# schSensorChassiNano.net
KiCad netlist of a schematic drawn in Altium Designer
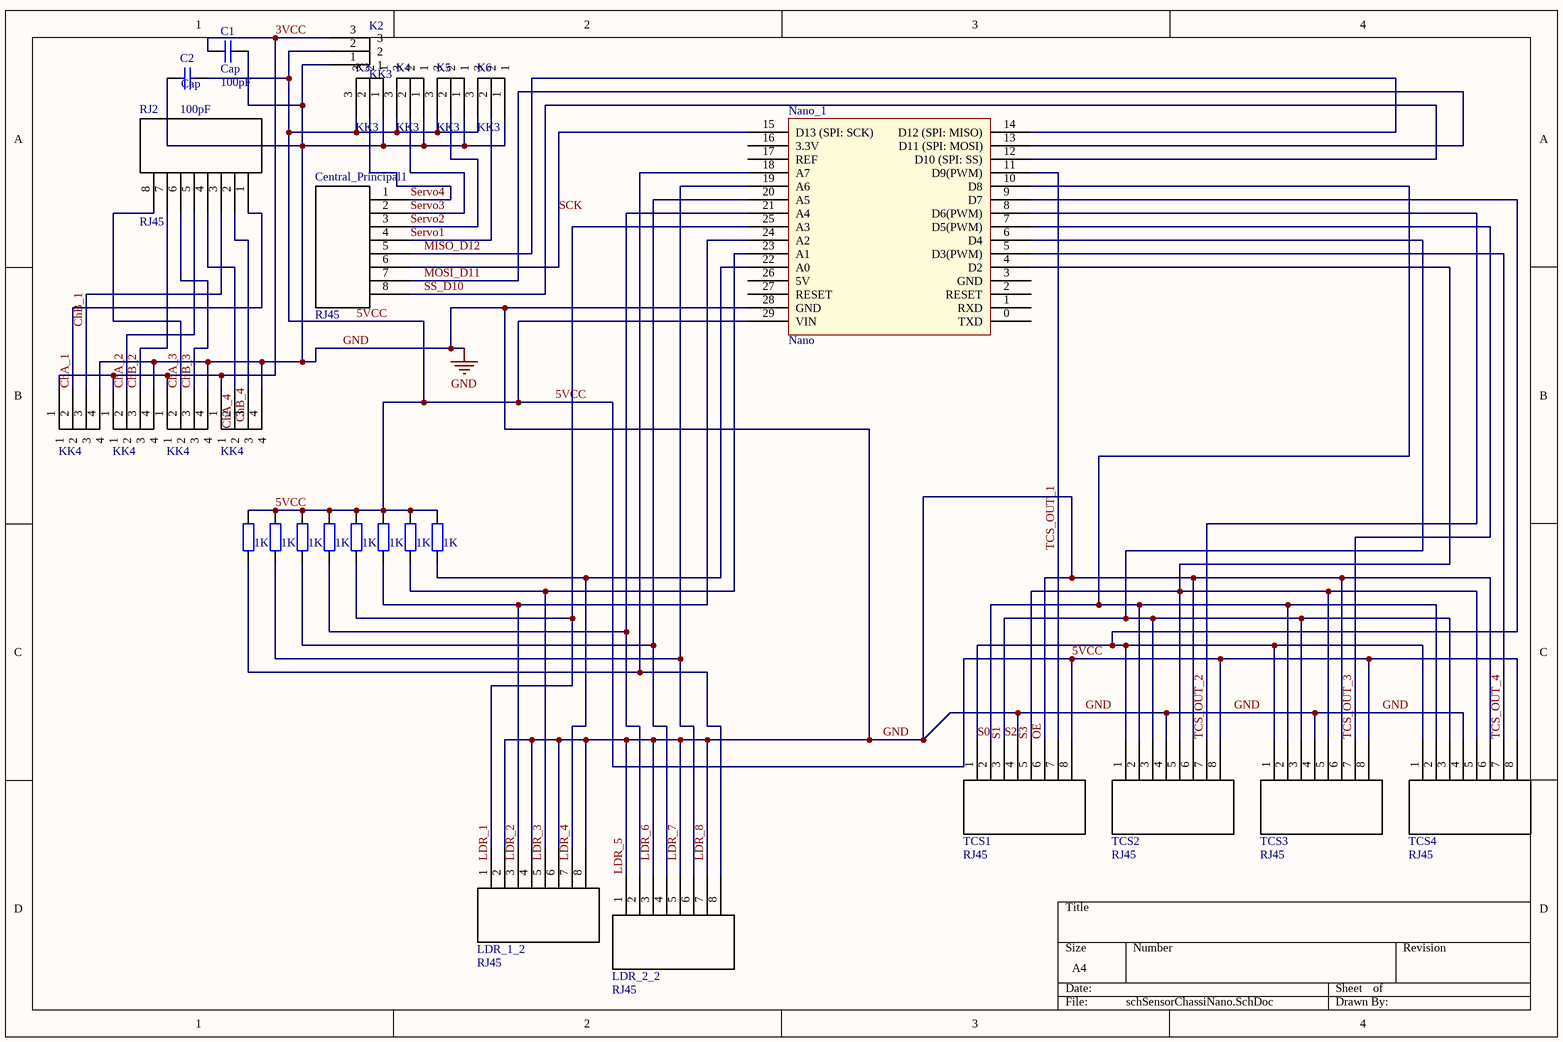
[diagram p0: schSensorChassiNano.SchDoc]

(export (version "E")
  (design (tool "Eeschema 10.0.6"))
  (components
    (comp (ref "C1")
      (value "Cap")
      (footprint "RAD-0.3")
      (description "Capacitor")
      (fields (field (name "ALTIUM_VALUE") "100pF") (field (name "PUBLISHER") "Altium Limited"))
      (libsource (lib "Miscellaneous Devices") (part "Cap"))
    )
    (comp (ref "C2")
      (value "Cap")
      (footprint "RAD-0.3")
      (description "Capacitor")
      (fields (field (name "ALTIUM_VALUE") "100pF") (field (name "PUBLISHER") "Altium Limited"))
      (libsource (lib "Miscellaneous Devices") (part "Cap"))
    )
    (comp (ref "Central_Principal1")
      (value "RJ45")
      (footprint "RJ45_Simples")
      (libsource (lib "Componentes_Open") (part "RJ45"))
    )
    (comp (ref "Encoder_4")
      (value "KK4")
      (footprint "4-vias")
      (libsource (lib "Componentes_Open") (part "KK4Vias"))
    )
    (comp (ref "Encoder_5")
      (value "KK4")
      (footprint "4-vias")
      (libsource (lib "Componentes_Open") (part "KK4Vias"))
    )
    (comp (ref "Encoder_6")
      (value "KK4")
      (footprint "4-vias")
      (libsource (lib "Componentes_Open") (part "KK4Vias"))
    )
    (comp (ref "K1") (value "KK4") (footprint "4-vias") (libsource (lib "Componentes_Open") (part "KK4Vias")))
    (comp (ref "K2") (value "KK3") (footprint "3-vias") (libsource (lib "Componentes_Open") (part "KK3Vias")))
    (comp (ref "K3") (value "KK3") (footprint "3-vias") (libsource (lib "Componentes_Open") (part "KK3Vias")))
    (comp (ref "K4") (value "KK3") (footprint "3-vias") (libsource (lib "Componentes_Open") (part "KK3Vias")))
    (comp (ref "K5") (value "KK3") (footprint "3-vias") (libsource (lib "Componentes_Open") (part "KK3Vias")))
    (comp (ref "K6") (value "KK3") (footprint "3-vias") (libsource (lib "Componentes_Open") (part "KK3Vias")))
    (comp (ref "LDR_1_2")
      (value "RJ45")
      (footprint "RJ45_Simples")
      (libsource (lib "Componentes_Open") (part "RJ45"))
    )
    (comp (ref "LDR_2_2")
      (value "RJ45")
      (footprint "RJ45_Simples")
      (libsource (lib "Componentes_Open") (part "RJ45"))
    )
    (comp (ref "Nano_1")
      (value "Nano")
      (footprint "Arduino_Nano")
      (libsource (lib "Componentes_Open") (part "Arduino_Nano"))
    )
    (comp (ref "R17")
      (value "1K")
      (footprint "AXIAL-0.4")
      (description "Resistor")
      (fields (field (name "Comment") "Res2") (field (name "PUBLISHER") "Altium Limited"))
      (libsource (lib "Miscellaneous Devices") (part "Res2"))
    )
    (comp (ref "R18")
      (value "1K")
      (footprint "AXIAL-0.4")
      (description "Resistor")
      (fields (field (name "Comment") "Res2") (field (name "PUBLISHER") "Altium Limited"))
      (libsource (lib "Miscellaneous Devices") (part "Res2"))
    )
    (comp (ref "R19")
      (value "1K")
      (footprint "AXIAL-0.4")
      (description "Resistor")
      (fields (field (name "Comment") "Res2") (field (name "PUBLISHER") "Altium Limited"))
      (libsource (lib "Miscellaneous Devices") (part "Res2"))
    )
    (comp (ref "R20")
      (value "1K")
      (footprint "AXIAL-0.4")
      (description "Resistor")
      (fields (field (name "Comment") "Res2") (field (name "PUBLISHER") "Altium Limited"))
      (libsource (lib "Miscellaneous Devices") (part "Res2"))
    )
    (comp (ref "R21")
      (value "1K")
      (footprint "AXIAL-0.4")
      (description "Resistor")
      (fields (field (name "Comment") "Res2") (field (name "PUBLISHER") "Altium Limited"))
      (libsource (lib "Miscellaneous Devices") (part "Res2"))
    )
    (comp (ref "R22")
      (value "1K")
      (footprint "AXIAL-0.4")
      (description "Resistor")
      (fields (field (name "Comment") "Res2") (field (name "PUBLISHER") "Altium Limited"))
      (libsource (lib "Miscellaneous Devices") (part "Res2"))
    )
    (comp (ref "R23")
      (value "1K")
      (footprint "AXIAL-0.4")
      (description "Resistor")
      (fields (field (name "Comment") "Res2") (field (name "PUBLISHER") "Altium Limited"))
      (libsource (lib "Miscellaneous Devices") (part "Res2"))
    )
    (comp (ref "R24")
      (value "1K")
      (footprint "AXIAL-0.4")
      (description "Resistor")
      (fields (field (name "Comment") "Res2") (field (name "PUBLISHER") "Altium Limited"))
      (libsource (lib "Miscellaneous Devices") (part "Res2"))
    )
    (comp (ref "RJ2")
      (value "RJ45")
      (footprint "RJ45_Simples")
      (libsource (lib "Componentes_Open") (part "RJ45"))
    )
    (comp (ref "TCS1")
      (value "RJ45")
      (footprint "RJ45_Simples")
      (libsource (lib "Componentes_Open") (part "RJ45"))
    )
    (comp (ref "TCS2")
      (value "RJ45")
      (footprint "RJ45_Simples")
      (libsource (lib "Componentes_Open") (part "RJ45"))
    )
    (comp (ref "TCS3")
      (value "RJ45")
      (footprint "RJ45_Simples")
      (libsource (lib "Componentes_Open") (part "RJ45"))
    )
    (comp (ref "TCS4")
      (value "RJ45")
      (footprint "RJ45_Simples")
      (libsource (lib "Componentes_Open") (part "RJ45"))
    )
  )
  (nets
    (net (code "1") (name "/3VCC") (class "Default")
      (node (ref "C1") (pin "1") (pinfunction "1_1") (pintype "passive"))
      (node (ref "Encoder_4") (pin "1") (pinfunction "1_1") (pintype "passive"))
      (node (ref "Encoder_5") (pin "1") (pinfunction "1_1") (pintype "passive"))
      (node (ref "Encoder_6") (pin "1") (pinfunction "1_1") (pintype "passive"))
      (node (ref "K1") (pin "1") (pinfunction "1_1") (pintype "passive"))
      (node (ref "K2") (pin "3") (pinfunction "3_3") (pintype "passive"))
    )
    (net (code "2") (name "/5VCC") (class "Default")
      (node (ref "C2") (pin "2") (pinfunction "2_2") (pintype "passive"))
      (node (ref "K2") (pin "2") (pinfunction "2_2") (pintype "passive"))
      (node (ref "K3") (pin "3") (pinfunction "3_3") (pintype "passive"))
      (node (ref "K4") (pin "3") (pinfunction "3_3") (pintype "passive"))
      (node (ref "K5") (pin "3") (pinfunction "3_3") (pintype "passive"))
      (node (ref "K6") (pin "3") (pinfunction "3_3") (pintype "passive"))
      (node (ref "Nano_1") (pin "29") (pinfunction "VIN_29") (pintype "passive"))
      (node (ref "R17") (pin "2") (pinfunction "2_2") (pintype "passive"))
      (node (ref "R18") (pin "2") (pinfunction "2_2") (pintype "passive"))
      (node (ref "R19") (pin "2") (pinfunction "2_2") (pintype "passive"))
      (node (ref "R20") (pin "2") (pinfunction "2_2") (pintype "passive"))
      (node (ref "R21") (pin "2") (pinfunction "2_2") (pintype "passive"))
      (node (ref "R22") (pin "2") (pinfunction "2_2") (pintype "passive"))
      (node (ref "R23") (pin "2") (pinfunction "2_2") (pintype "passive"))
      (node (ref "R24") (pin "2") (pinfunction "2_2") (pintype "passive"))
      (node (ref "TCS1") (pin "8") (pinfunction "8_8") (pintype "passive"))
      (node (ref "TCS2") (pin "8") (pinfunction "8_8") (pintype "passive"))
      (node (ref "TCS3") (pin "8") (pinfunction "8_8") (pintype "passive"))
      (node (ref "TCS4") (pin "8") (pinfunction "8_8") (pintype "passive"))
    )
    (net (code "3") (name "/ChA_1") (class "Default")
      (node (ref "K1") (pin "2") (pinfunction "2_2") (pintype "passive"))
      (node (ref "RJ2") (pin "1") (pinfunction "9_1") (pintype "passive"))
    )
    (net (code "4") (name "/ChA_2") (class "Default")
      (node (ref "Encoder_4") (pin "2") (pinfunction "2_2") (pintype "passive"))
      (node (ref "RJ2") (pin "5") (pinfunction "5_5") (pintype "passive"))
    )
    (net (code "5") (name "/ChA_3") (class "Default")
      (node (ref "Encoder_5") (pin "2") (pinfunction "2_2") (pintype "passive"))
      (node (ref "RJ2") (pin "8") (pinfunction "8_8") (pintype "passive"))
    )
    (net (code "7") (name "/ChB_1") (class "Default")
      (node (ref "K1") (pin "3") (pinfunction "3_3") (pintype "passive"))
      (node (ref "RJ2") (pin "3") (pinfunction "3_3") (pintype "passive"))
    )
    (net (code "8") (name "/ChB_2") (class "Default")
      (node (ref "Encoder_4") (pin "3") (pinfunction "3_3") (pintype "passive"))
      (node (ref "RJ2") (pin "7") (pinfunction "7_7") (pintype "passive"))
    )
    (net (code "9") (name "/ChB_3") (class "Default")
      (node (ref "Encoder_5") (pin "3") (pinfunction "3_3") (pintype "passive"))
      (node (ref "RJ2") (pin "6") (pinfunction "6_6") (pintype "passive"))
    )
    (net (code "15") (name "/MISO_D12") (class "Default")
      (node (ref "Central_Principal1") (pin "5") (pinfunction "5_5") (pintype "passive"))
      (node (ref "Nano_1") (pin "14") (pinfunction "D12_(SPI:_MISO)_14") (pintype "passive"))
    )
    (net (code "16") (name "/MOSI_D11") (class "Default")
      (node (ref "Central_Principal1") (pin "7") (pinfunction "7_7") (pintype "passive"))
      (node (ref "Nano_1") (pin "13") (pinfunction "D11_(SPI:_MOSI)_13") (pintype "passive"))
    )
    (net (code "17") (name "/S0") (class "Default")
      (node (ref "Nano_1") (pin "9") (pinfunction "D7_9") (pintype "passive"))
      (node (ref "TCS1") (pin "1") (pinfunction "9_1") (pintype "passive"))
      (node (ref "TCS2") (pin "1") (pinfunction "9_1") (pintype "passive"))
      (node (ref "TCS3") (pin "1") (pinfunction "9_1") (pintype "passive"))
      (node (ref "TCS4") (pin "1") (pinfunction "9_1") (pintype "passive"))
    )
    (net (code "18") (name "/S1") (class "Default")
      (node (ref "Nano_1") (pin "6") (pinfunction "D4_6") (pintype "passive"))
      (node (ref "TCS1") (pin "3") (pinfunction "3_3") (pintype "passive"))
      (node (ref "TCS2") (pin "3") (pinfunction "3_3") (pintype "passive"))
      (node (ref "TCS3") (pin "3") (pinfunction "3_3") (pintype "passive"))
      (node (ref "TCS4") (pin "3") (pinfunction "3_3") (pintype "passive"))
    )
    (net (code "19") (name "/S3") (class "Default")
      (node (ref "Nano_1") (pin "4") (pinfunction "D2_4") (pintype "passive"))
      (node (ref "TCS1") (pin "5") (pinfunction "5_5") (pintype "passive"))
      (node (ref "TCS2") (pin "5") (pinfunction "5_5") (pintype "passive"))
      (node (ref "TCS3") (pin "5") (pinfunction "5_5") (pintype "passive"))
      (node (ref "TCS4") (pin "5") (pinfunction "5_5") (pintype "passive"))
    )
    (net (code "20") (name "/SCK") (class "Default")
      (node (ref "Central_Principal1") (pin "6") (pinfunction "6_6") (pintype "passive"))
      (node (ref "Nano_1") (pin "15") (pinfunction "D13_(SPI:_SCK)_15") (pintype "passive"))
    )
    (net (code "21") (name "/SS_D10") (class "Default")
      (node (ref "Central_Principal1") (pin "8") (pinfunction "8_8") (pintype "passive"))
      (node (ref "Nano_1") (pin "12") (pinfunction "D10_(SPI:_SS)_12") (pintype "passive"))
    )
    (net (code "22") (name "/Servo1") (class "Default")
      (node (ref "Central_Principal1") (pin "4") (pinfunction "4_4") (pintype "passive"))
      (node (ref "K6") (pin "2") (pinfunction "2_2") (pintype "passive"))
    )
    (net (code "23") (name "/Servo2") (class "Default")
      (node (ref "Central_Principal1") (pin "3") (pinfunction "3_3") (pintype "passive"))
      (node (ref "K5") (pin "2") (pinfunction "2_2") (pintype "passive"))
    )
    (net (code "24") (name "/Servo3") (class "Default")
      (node (ref "Central_Principal1") (pin "2") (pinfunction "2_2") (pintype "passive"))
      (node (ref "K4") (pin "2") (pinfunction "2_2") (pintype "passive"))
    )
    (net (code "25") (name "/Servo4") (class "Default")
      (node (ref "Central_Principal1") (pin "1") (pinfunction "9_1") (pintype "passive"))
      (node (ref "K3") (pin "2") (pinfunction "2_2") (pintype "passive"))
    )
    (net (code "26") (name "/TCS_OUT_1") (class "Default")
      (node (ref "Nano_1") (pin "11") (pinfunction "D9(PWM)_11") (pintype "passive"))
      (node (ref "TCS1") (pin "7") (pinfunction "7_7") (pintype "passive"))
    )
    (net (code "27") (name "/TCS_OUT_2") (class "Default")
      (node (ref "Nano_1") (pin "8") (pinfunction "D6(PWM)_8") (pintype "passive"))
      (node (ref "TCS2") (pin "7") (pinfunction "7_7") (pintype "passive"))
    )
    (net (code "28") (name "/TCS_OUT_3") (class "Default")
      (node (ref "Nano_1") (pin "7") (pinfunction "D5(PWM)_7") (pintype "passive"))
      (node (ref "TCS3") (pin "7") (pinfunction "7_7") (pintype "passive"))
    )
    (net (code "29") (name "/TCS_OUT_4") (class "Default")
      (node (ref "Nano_1") (pin "5") (pinfunction "D3(PWM)_5") (pintype "passive"))
      (node (ref "TCS4") (pin "7") (pinfunction "7_7") (pintype "passive"))
    )
    (net (code "30") (name "GND") (class "Default")
      (node (ref "C1") (pin "2") (pinfunction "2_2") (pintype "passive"))
      (node (ref "C2") (pin "1") (pinfunction "1_1") (pintype "passive"))
      (node (ref "Encoder_4") (pin "4") (pinfunction "4_4") (pintype "passive"))
      (node (ref "Encoder_5") (pin "4") (pinfunction "4_4") (pintype "passive"))
      (node (ref "Encoder_6") (pin "4") (pinfunction "4_4") (pintype "passive"))
      (node (ref "K1") (pin "4") (pinfunction "4_4") (pintype "passive"))
      (node (ref "K2") (pin "1") (pinfunction "1_1") (pintype "passive"))
      (node (ref "K3") (pin "1") (pinfunction "1_1") (pintype "passive"))
      (node (ref "K4") (pin "1") (pinfunction "1_1") (pintype "passive"))
      (node (ref "K5") (pin "1") (pinfunction "1_1") (pintype "passive"))
      (node (ref "K6") (pin "1") (pinfunction "1_1") (pintype "passive"))
      (node (ref "LDR_1_2") (pin "2") (pinfunction "2_2") (pintype "passive"))
      (node (ref "LDR_1_2") (pin "4") (pinfunction "4_4") (pintype "passive"))
      (node (ref "LDR_1_2") (pin "6") (pinfunction "6_6") (pintype "passive"))
      (node (ref "LDR_1_2") (pin "8") (pinfunction "8_8") (pintype "passive"))
      (node (ref "LDR_2_2") (pin "1") (pinfunction "9_1") (pintype "passive"))
      (node (ref "LDR_2_2") (pin "3") (pinfunction "3_3") (pintype "passive"))
      (node (ref "LDR_2_2") (pin "5") (pinfunction "5_5") (pintype "passive"))
      (node (ref "LDR_2_2") (pin "7") (pinfunction "7_7") (pintype "passive"))
      (node (ref "Nano_1") (pin "28") (pinfunction "GND_28") (pintype "passive"))
      (node (ref "TCS1") (pin "4") (pinfunction "4_4") (pintype "passive"))
      (node (ref "TCS1") (pin "6") (pinfunction "6_6") (pintype "passive"))
      (node (ref "TCS2") (pin "4") (pinfunction "4_4") (pintype "passive"))
      (node (ref "TCS2") (pin "6") (pinfunction "6_6") (pintype "passive"))
      (node (ref "TCS3") (pin "4") (pinfunction "4_4") (pintype "passive"))
      (node (ref "TCS3") (pin "6") (pinfunction "6_6") (pintype "passive"))
      (node (ref "TCS4") (pin "4") (pinfunction "4_4") (pintype "passive"))
      (node (ref "TCS4") (pin "6") (pinfunction "6_6") (pintype "passive"))
    )
    (net (code "31") (name "Net-(Encoder_6-Pad2)") (class "Default")
      (node (ref "Encoder_6") (pin "2") (pinfunction "2_2") (pintype "passive"))
      (node (ref "RJ2") (pin "4") (pinfunction "4_4") (pintype "passive"))
    )
    (net (code "32") (name "Net-(Encoder_6-Pad3)") (class "Default")
      (node (ref "Encoder_6") (pin "3") (pinfunction "3_3") (pintype "passive"))
      (node (ref "RJ2") (pin "2") (pinfunction "2_2") (pintype "passive"))
    )
    (net (code "33") (name "Net-(LDR_1_2-9)") (class "Default")
      (node (ref "LDR_1_2") (pin "1") (pinfunction "9_1") (pintype "passive"))
      (node (ref "Nano_1") (pin "25") (pinfunction "A3_25") (pintype "passive"))
      (node (ref "R21") (pin "1") (pinfunction "1_1") (pintype "passive"))
    )
    (net (code "34") (name "Net-(Nano_1-A0)") (class "Default")
      (node (ref "LDR_1_2") (pin "7") (pinfunction "7_7") (pintype "passive"))
      (node (ref "Nano_1") (pin "22") (pinfunction "A0_22") (pintype "passive"))
      (node (ref "R24") (pin "1") (pinfunction "1_1") (pintype "passive"))
    )
    (net (code "35") (name "Net-(Nano_1-A1)") (class "Default")
      (node (ref "LDR_1_2") (pin "5") (pinfunction "5_5") (pintype "passive"))
      (node (ref "Nano_1") (pin "23") (pinfunction "A1_23") (pintype "passive"))
      (node (ref "R23") (pin "1") (pinfunction "1_1") (pintype "passive"))
    )
    (net (code "36") (name "Net-(Nano_1-A2)") (class "Default")
      (node (ref "LDR_1_2") (pin "3") (pinfunction "3_3") (pintype "passive"))
      (node (ref "Nano_1") (pin "24") (pinfunction "A2_24") (pintype "passive"))
      (node (ref "R22") (pin "1") (pinfunction "1_1") (pintype "passive"))
    )
    (net (code "37") (name "Net-(Nano_1-A4)") (class "Default")
      (node (ref "LDR_2_2") (pin "2") (pinfunction "2_2") (pintype "passive"))
      (node (ref "Nano_1") (pin "21") (pinfunction "A4_21") (pintype "passive"))
      (node (ref "R20") (pin "1") (pinfunction "1_1") (pintype "passive"))
    )
    (net (code "38") (name "Net-(Nano_1-A5)") (class "Default")
      (node (ref "LDR_2_2") (pin "4") (pinfunction "4_4") (pintype "passive"))
      (node (ref "Nano_1") (pin "20") (pinfunction "A5_20") (pintype "passive"))
      (node (ref "R19") (pin "1") (pinfunction "1_1") (pintype "passive"))
    )
    (net (code "39") (name "Net-(Nano_1-A6)") (class "Default")
      (node (ref "LDR_2_2") (pin "6") (pinfunction "6_6") (pintype "passive"))
      (node (ref "Nano_1") (pin "19") (pinfunction "A6_19") (pintype "passive"))
      (node (ref "R18") (pin "1") (pinfunction "1_1") (pintype "passive"))
    )
    (net (code "40") (name "Net-(Nano_1-A7)") (class "Default")
      (node (ref "LDR_2_2") (pin "8") (pinfunction "8_8") (pintype "passive"))
      (node (ref "Nano_1") (pin "18") (pinfunction "A7_18") (pintype "passive"))
      (node (ref "R17") (pin "1") (pinfunction "1_1") (pintype "passive"))
    )
    (net (code "41") (name "Net-(Nano_1-D8)") (class "Default")
      (node (ref "Nano_1") (pin "10") (pinfunction "D8_10") (pintype "passive"))
      (node (ref "TCS1") (pin "2") (pinfunction "2_2") (pintype "passive"))
      (node (ref "TCS2") (pin "2") (pinfunction "2_2") (pintype "passive"))
      (node (ref "TCS3") (pin "2") (pinfunction "2_2") (pintype "passive"))
      (node (ref "TCS4") (pin "2") (pinfunction "2_2") (pintype "passive"))
    )
    (net (code "42") (name "unconnected-(Nano_1-3.3V-Pad16)") (class "Default")
      (node (ref "Nano_1") (pin "16") (pinfunction "3.3V_16") (pintype "passive"))
    )
    (net (code "43") (name "unconnected-(Nano_1-5V-Pad26)") (class "Default")
      (node (ref "Nano_1") (pin "26") (pinfunction "5V_26") (pintype "passive"))
    )
    (net (code "44") (name "unconnected-(Nano_1-GND-Pad3)") (class "Default")
      (node (ref "Nano_1") (pin "3") (pinfunction "GND_3") (pintype "passive"))
    )
    (net (code "45") (name "unconnected-(Nano_1-REF-Pad17)") (class "Default")
      (node (ref "Nano_1") (pin "17") (pinfunction "REF_17") (pintype "passive"))
    )
    (net (code "46") (name "unconnected-(Nano_1-RESET-Pad2)") (class "Default")
      (node (ref "Nano_1") (pin "2") (pinfunction "RESET_2") (pintype "passive"))
    )
    (net (code "47") (name "unconnected-(Nano_1-RESET-Pad27)") (class "Default")
      (node (ref "Nano_1") (pin "27") (pinfunction "RESET_27") (pintype "passive"))
    )
    (net (code "48") (name "unconnected-(Nano_1-RXD-Pad1)") (class "Default")
      (node (ref "Nano_1") (pin "1") (pinfunction "RXD_1") (pintype "passive"))
    )
    (net (code "49") (name "unconnected-(Nano_1-TXD-Pad0)") (class "Default")
      (node (ref "Nano_1") (pin "0") (pinfunction "TXD_0") (pintype "passive"))
    )
  )
)
